# schematic.net
KiCad netlist of a schematic drawn in EAGLE
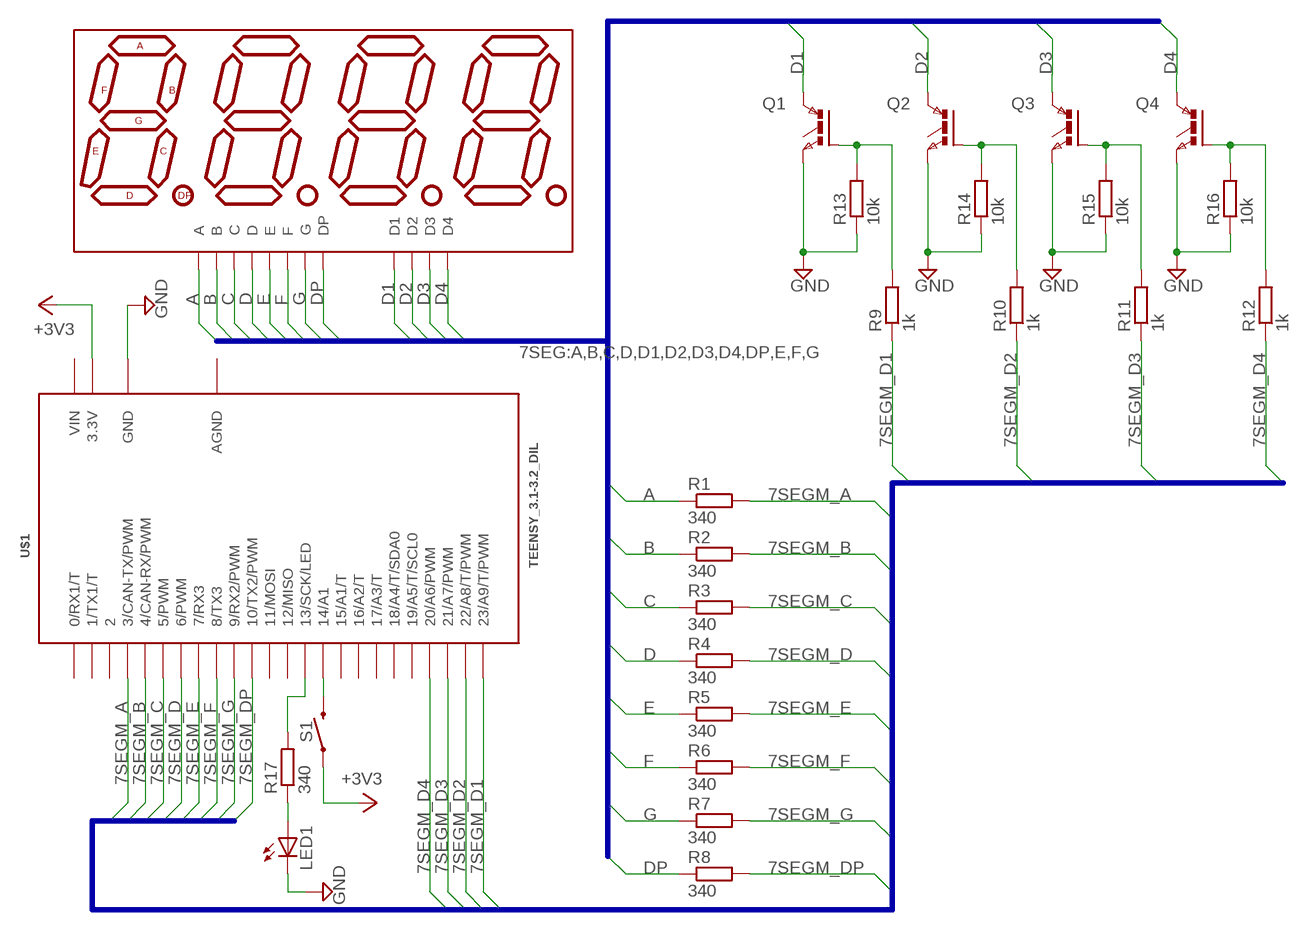
[diagram p0: schematic, sheet 1]

(export (version "E")
  (design (tool "Eeschema 10.0.6"))
  (components
    (comp (ref "DISP1")
      (value "7-SEGMENT-4DIGIT-COUNTER-HP-BUBBLE")
      (footprint "eagle-import:DIL12")
      (libsource (lib "eagle-import") (part "7-SEGMENT-4DIGIT-COUNTER-HP-BUBBLE"))
    )
    (comp (ref "LED1")
      (value "LED_ELD260")
      (footprint "eagle-import:LED_LD260")
      (libsource (lib "eagle-import") (part "LED_ELD260"))
    )
    (comp (ref "Q1")
      (value "IGBTTO251AA")
      (footprint "eagle-import:TO251AA")
      (libsource (lib "eagle-import") (part "IGBTTO251AA"))
    )
    (comp (ref "Q2")
      (value "IGBTTO251AA")
      (footprint "eagle-import:TO251AA")
      (libsource (lib "eagle-import") (part "IGBTTO251AA"))
    )
    (comp (ref "Q3")
      (value "IGBTTO251AA")
      (footprint "eagle-import:TO251AA")
      (libsource (lib "eagle-import") (part "IGBTTO251AA"))
    )
    (comp (ref "Q4")
      (value "IGBTTO251AA")
      (footprint "eagle-import:TO251AA")
      (libsource (lib "eagle-import") (part "IGBTTO251AA"))
    )
    (comp (ref "R1")
      (value "340")
      (footprint "eagle-import:0204_5")
      (libsource (lib "eagle-import") (part "R-EU_0204/5"))
    )
    (comp (ref "R2")
      (value "340")
      (footprint "eagle-import:0204_5")
      (libsource (lib "eagle-import") (part "R-EU_0204/5"))
    )
    (comp (ref "R3")
      (value "340")
      (footprint "eagle-import:0204_5")
      (libsource (lib "eagle-import") (part "R-EU_0204/5"))
    )
    (comp (ref "R4")
      (value "340")
      (footprint "eagle-import:0204_5")
      (libsource (lib "eagle-import") (part "R-EU_0204/5"))
    )
    (comp (ref "R5")
      (value "340")
      (footprint "eagle-import:0204_5")
      (libsource (lib "eagle-import") (part "R-EU_0204/5"))
    )
    (comp (ref "R6")
      (value "340")
      (footprint "eagle-import:0204_5")
      (libsource (lib "eagle-import") (part "R-EU_0204/5"))
    )
    (comp (ref "R7")
      (value "340")
      (footprint "eagle-import:0204_5")
      (libsource (lib "eagle-import") (part "R-EU_0204/5"))
    )
    (comp (ref "R8")
      (value "340")
      (footprint "eagle-import:0204_5")
      (libsource (lib "eagle-import") (part "R-EU_0204/5"))
    )
    (comp (ref "R9")
      (value "1k")
      (footprint "eagle-import:0204_5")
      (libsource (lib "eagle-import") (part "R-EU_0204/5"))
    )
    (comp (ref "R10")
      (value "1k")
      (footprint "eagle-import:0204_5")
      (libsource (lib "eagle-import") (part "R-EU_0204/5"))
    )
    (comp (ref "R11")
      (value "1k")
      (footprint "eagle-import:0204_5")
      (libsource (lib "eagle-import") (part "R-EU_0204/5"))
    )
    (comp (ref "R12")
      (value "1k")
      (footprint "eagle-import:0204_5")
      (libsource (lib "eagle-import") (part "R-EU_0204/5"))
    )
    (comp (ref "R13")
      (value "10k")
      (footprint "eagle-import:0204_5")
      (libsource (lib "eagle-import") (part "R-EU_0204/5"))
    )
    (comp (ref "R14")
      (value "10k")
      (footprint "eagle-import:0204_5")
      (libsource (lib "eagle-import") (part "R-EU_0204/5"))
    )
    (comp (ref "R15")
      (value "10k")
      (footprint "eagle-import:0204_5")
      (libsource (lib "eagle-import") (part "R-EU_0204/5"))
    )
    (comp (ref "R16")
      (value "10k")
      (footprint "eagle-import:0204_5")
      (libsource (lib "eagle-import") (part "R-EU_0204/5"))
    )
    (comp (ref "R17")
      (value "340")
      (footprint "eagle-import:0204_5")
      (libsource (lib "eagle-import") (part "R-EU_0204/5"))
    )
    (comp (ref "S1")
      (value "MOMENTARY-SWITCH-SPST-PTH-6.0MM")
      (footprint "eagle-import:TACTILE_SWITCH_PTH_6.0MM")
      (libsource (lib "eagle-import") (part "MOMENTARY-SWITCH-SPST-PTH-6.0MM"))
    )
    (comp (ref "U$1")
      (value "TEENSY_3.1-3.2_DIL")
      (footprint "eagle-import:TEENSY_3.0-3.2&LC_DIL")
      (libsource (lib "eagle-import") (part "TEENSY_3.1-3.2_DIL"))
    )
  )
  (nets
    (net (code "2") (name "+3V3") (class "Default")
      (node (ref "S1") (pin "1") (pinfunction "1_1") (pintype "passive"))
      (node (ref "U$1") (pin "3.3V") (pinfunction "3.3V_3.3V") (pintype "power_in"))
    )
    (net (code "3") (name "/7SEGM_A") (class "Default")
      (node (ref "R1") (pin "2") (pinfunction "2_2") (pintype "passive"))
      (node (ref "U$1") (pin "3") (pinfunction "3/CAN-TX/PWM_3") (pintype "bidirectional"))
    )
    (net (code "4") (name "/7SEGM_B") (class "Default")
      (node (ref "R2") (pin "2") (pinfunction "2_2") (pintype "passive"))
      (node (ref "U$1") (pin "4") (pinfunction "4/CAN-RX/PWM_4") (pintype "bidirectional"))
    )
    (net (code "5") (name "/7SEGM_C") (class "Default")
      (node (ref "R3") (pin "2") (pinfunction "2_2") (pintype "passive"))
      (node (ref "U$1") (pin "5") (pinfunction "5/PWM_5") (pintype "bidirectional"))
    )
    (net (code "6") (name "/7SEGM_D") (class "Default")
      (node (ref "R4") (pin "2") (pinfunction "2_2") (pintype "passive"))
      (node (ref "U$1") (pin "6") (pinfunction "6/PWM_6") (pintype "bidirectional"))
    )
    (net (code "7") (name "/7SEGM_D1") (class "Default")
      (node (ref "R9") (pin "1") (pinfunction "1_1") (pintype "passive"))
      (node (ref "U$1") (pin "23/A9") (pinfunction "23/A9/T/PWM_23/A9") (pintype "bidirectional"))
    )
    (net (code "8") (name "/7SEGM_D2") (class "Default")
      (node (ref "R10") (pin "1") (pinfunction "1_1") (pintype "passive"))
      (node (ref "U$1") (pin "22/A8") (pinfunction "22/A8/T/PWM_22/A8") (pintype "bidirectional"))
    )
    (net (code "9") (name "/7SEGM_D3") (class "Default")
      (node (ref "R11") (pin "1") (pinfunction "1_1") (pintype "passive"))
      (node (ref "U$1") (pin "21/A7") (pinfunction "21/A7/PWM_21/A7") (pintype "bidirectional"))
    )
    (net (code "10") (name "/7SEGM_D4") (class "Default")
      (node (ref "R12") (pin "1") (pinfunction "1_1") (pintype "passive"))
      (node (ref "U$1") (pin "20/A6") (pinfunction "20/A6/PWM_20/A6") (pintype "bidirectional"))
    )
    (net (code "11") (name "/7SEGM_DP") (class "Default")
      (node (ref "R8") (pin "2") (pinfunction "2_2") (pintype "passive"))
      (node (ref "U$1") (pin "10") (pinfunction "10/TX2/PWM_10") (pintype "bidirectional"))
    )
    (net (code "12") (name "/7SEGM_E") (class "Default")
      (node (ref "R5") (pin "2") (pinfunction "2_2") (pintype "passive"))
      (node (ref "U$1") (pin "7") (pinfunction "7/RX3_7") (pintype "bidirectional"))
    )
    (net (code "13") (name "/7SEGM_F") (class "Default")
      (node (ref "R6") (pin "2") (pinfunction "2_2") (pintype "passive"))
      (node (ref "U$1") (pin "8") (pinfunction "8/TX3_8") (pintype "bidirectional"))
    )
    (net (code "14") (name "/7SEGM_G") (class "Default")
      (node (ref "R7") (pin "2") (pinfunction "2_2") (pintype "passive"))
      (node (ref "U$1") (pin "9") (pinfunction "9/RX2/PWM_9") (pintype "bidirectional"))
    )
    (net (code "15") (name "/A") (class "Default")
      (node (ref "DISP1") (pin "12") (pinfunction "A_12") (pintype "bidirectional"))
      (node (ref "R1") (pin "1") (pinfunction "1_1") (pintype "passive"))
    )
    (net (code "16") (name "/AGND") (class "Default")
      (node (ref "U$1") (pin "AGND") (pinfunction "AGND_AGND") (pintype "power_in"))
    )
    (net (code "17") (name "/B") (class "Default")
      (node (ref "DISP1") (pin "11") (pinfunction "B_11") (pintype "bidirectional"))
      (node (ref "R2") (pin "1") (pinfunction "1_1") (pintype "passive"))
    )
    (net (code "18") (name "/C") (class "Default")
      (node (ref "DISP1") (pin "3") (pinfunction "C_3") (pintype "bidirectional"))
      (node (ref "R3") (pin "1") (pinfunction "1_1") (pintype "passive"))
    )
    (net (code "19") (name "/D") (class "Default")
      (node (ref "DISP1") (pin "8") (pinfunction "D_8") (pintype "bidirectional"))
      (node (ref "R4") (pin "1") (pinfunction "1_1") (pintype "passive"))
    )
    (net (code "20") (name "/D1") (class "Default")
      (node (ref "DISP1") (pin "1") (pinfunction "D1_1") (pintype "bidirectional"))
      (node (ref "Q1") (pin "2") (pinfunction "C_2") (pintype "passive"))
    )
    (net (code "21") (name "/D2") (class "Default")
      (node (ref "DISP1") (pin "10") (pinfunction "D2_10") (pintype "bidirectional"))
      (node (ref "Q2") (pin "2") (pinfunction "C_2") (pintype "passive"))
    )
    (net (code "22") (name "/D3") (class "Default")
      (node (ref "DISP1") (pin "4") (pinfunction "D3_4") (pintype "bidirectional"))
      (node (ref "Q3") (pin "2") (pinfunction "C_2") (pintype "passive"))
    )
    (net (code "23") (name "/D4") (class "Default")
      (node (ref "DISP1") (pin "6") (pinfunction "D4_6") (pintype "bidirectional"))
      (node (ref "Q4") (pin "2") (pinfunction "C_2") (pintype "passive"))
    )
    (net (code "24") (name "/DP") (class "Default")
      (node (ref "DISP1") (pin "5") (pinfunction "DP_5") (pintype "bidirectional"))
      (node (ref "R8") (pin "1") (pinfunction "1_1") (pintype "passive"))
    )
    (net (code "25") (name "/E") (class "Default")
      (node (ref "DISP1") (pin "2") (pinfunction "E_2") (pintype "bidirectional"))
      (node (ref "R5") (pin "1") (pinfunction "1_1") (pintype "passive"))
    )
    (net (code "26") (name "/F") (class "Default")
      (node (ref "DISP1") (pin "9") (pinfunction "F_9") (pintype "bidirectional"))
      (node (ref "R6") (pin "1") (pinfunction "1_1") (pintype "passive"))
    )
    (net (code "27") (name "/G") (class "Default")
      (node (ref "DISP1") (pin "7") (pinfunction "G_7") (pintype "bidirectional"))
      (node (ref "R7") (pin "1") (pinfunction "1_1") (pintype "passive"))
    )
    (net (code "28") (name "/VIN") (class "Default")
      (node (ref "U$1") (pin "VIN") (pinfunction "VIN_VIN") (pintype "power_in"))
    )
    (net (code "30") (name "GND") (class "Default")
      (node (ref "LED1") (pin "K") (pinfunction "C_K") (pintype "passive"))
      (node (ref "Q1") (pin "3") (pinfunction "E_3") (pintype "passive"))
      (node (ref "Q2") (pin "3") (pinfunction "E_3") (pintype "passive"))
      (node (ref "Q3") (pin "3") (pinfunction "E_3") (pintype "passive"))
      (node (ref "Q4") (pin "3") (pinfunction "E_3") (pintype "passive"))
      (node (ref "R13") (pin "1") (pinfunction "1_1") (pintype "passive"))
      (node (ref "R14") (pin "1") (pinfunction "1_1") (pintype "passive"))
      (node (ref "R15") (pin "1") (pinfunction "1_1") (pintype "passive"))
      (node (ref "R16") (pin "1") (pinfunction "1_1") (pintype "passive"))
      (node (ref "U$1") (pin "GND") (pinfunction "GND_GND") (pintype "power_in"))
    )
    (net (code "31") (name "Net-(LED1-PadA)") (class "Default")
      (node (ref "LED1") (pin "A") (pinfunction "A_A") (pintype "passive"))
      (node (ref "R17") (pin "1") (pinfunction "1_1") (pintype "passive"))
    )
    (net (code "32") (name "Net-(Q1-G)") (class "Default")
      (node (ref "Q1") (pin "1") (pinfunction "G_1") (pintype "passive"))
      (node (ref "R13") (pin "2") (pinfunction "2_2") (pintype "passive"))
      (node (ref "R9") (pin "2") (pinfunction "2_2") (pintype "passive"))
    )
    (net (code "33") (name "Net-(Q2-G)") (class "Default")
      (node (ref "Q2") (pin "1") (pinfunction "G_1") (pintype "passive"))
      (node (ref "R10") (pin "2") (pinfunction "2_2") (pintype "passive"))
      (node (ref "R14") (pin "2") (pinfunction "2_2") (pintype "passive"))
    )
    (net (code "34") (name "Net-(Q3-G)") (class "Default")
      (node (ref "Q3") (pin "1") (pinfunction "G_1") (pintype "passive"))
      (node (ref "R11") (pin "2") (pinfunction "2_2") (pintype "passive"))
      (node (ref "R15") (pin "2") (pinfunction "2_2") (pintype "passive"))
    )
    (net (code "35") (name "Net-(Q4-G)") (class "Default")
      (node (ref "Q4") (pin "1") (pinfunction "G_1") (pintype "passive"))
      (node (ref "R12") (pin "2") (pinfunction "2_2") (pintype "passive"))
      (node (ref "R16") (pin "2") (pinfunction "2_2") (pintype "passive"))
    )
    (net (code "36") (name "Net-(S1-2)") (class "Default")
      (node (ref "S1") (pin "3") (pinfunction "2_3") (pintype "passive"))
      (node (ref "U$1") (pin "14/A0") (pinfunction "14/A1_14/A0") (pintype "bidirectional"))
    )
    (net (code "37") (name "Net-(U$1-13{slash}SCK{slash}LED)") (class "Default")
      (node (ref "R17") (pin "2") (pinfunction "2_2") (pintype "passive"))
      (node (ref "U$1") (pin "13") (pinfunction "13/SCK/LED_13") (pintype "bidirectional"))
    )
    (net (code "38") (name "unconnected-(U$1-0{slash}RX1{slash}T-Pad0)") (class "Default")
      (node (ref "U$1") (pin "0") (pinfunction "0/RX1/T_0") (pintype "bidirectional"))
    )
    (net (code "39") (name "unconnected-(U$1-1{slash}TX1{slash}T-Pad1)") (class "Default")
      (node (ref "U$1") (pin "1") (pinfunction "1/TX1/T_1") (pintype "bidirectional"))
    )
    (net (code "40") (name "unconnected-(U$1-11{slash}MOSI-Pad11)") (class "Default")
      (node (ref "U$1") (pin "11") (pinfunction "11/MOSI_11") (pintype "bidirectional"))
    )
    (net (code "41") (name "unconnected-(U$1-12{slash}MISO-Pad12)") (class "Default")
      (node (ref "U$1") (pin "12") (pinfunction "12/MISO_12") (pintype "bidirectional"))
    )
    (net (code "42") (name "unconnected-(U$1-15{slash}A1{slash}T-Pad15{slash}A1)") (class "Default")
      (node (ref "U$1") (pin "15/A1") (pinfunction "15/A1/T_15/A1") (pintype "bidirectional"))
    )
    (net (code "43") (name "unconnected-(U$1-16{slash}A2{slash}T-Pad16{slash}A2)") (class "Default")
      (node (ref "U$1") (pin "16/A2") (pinfunction "16/A2/T_16/A2") (pintype "bidirectional"))
    )
    (net (code "44") (name "unconnected-(U$1-17{slash}A3{slash}T-Pad17{slash}A3)") (class "Default")
      (node (ref "U$1") (pin "17/A3") (pinfunction "17/A3/T_17/A3") (pintype "bidirectional"))
    )
    (net (code "45") (name "unconnected-(U$1-18{slash}A4{slash}T{slash}SDA0-Pad18{slash}A4)") (class "Default")
      (node (ref "U$1") (pin "18/A4") (pinfunction "18/A4/T/SDA0_18/A4") (pintype "bidirectional"))
    )
    (net (code "46") (name "unconnected-(U$1-19{slash}A5{slash}T{slash}SCL0-Pad19{slash}A5)") (class "Default")
      (node (ref "U$1") (pin "19/A5") (pinfunction "19/A5/T/SCL0_19/A5") (pintype "bidirectional"))
    )
    (net (code "47") (name "unconnected-(U$1-Pad2)") (class "Default")
      (node (ref "U$1") (pin "2") (pinfunction "2_2") (pintype "bidirectional"))
    )
  )
)
